# i2c0.net
KiCad netlist of a schematic drawn in Altium Designer
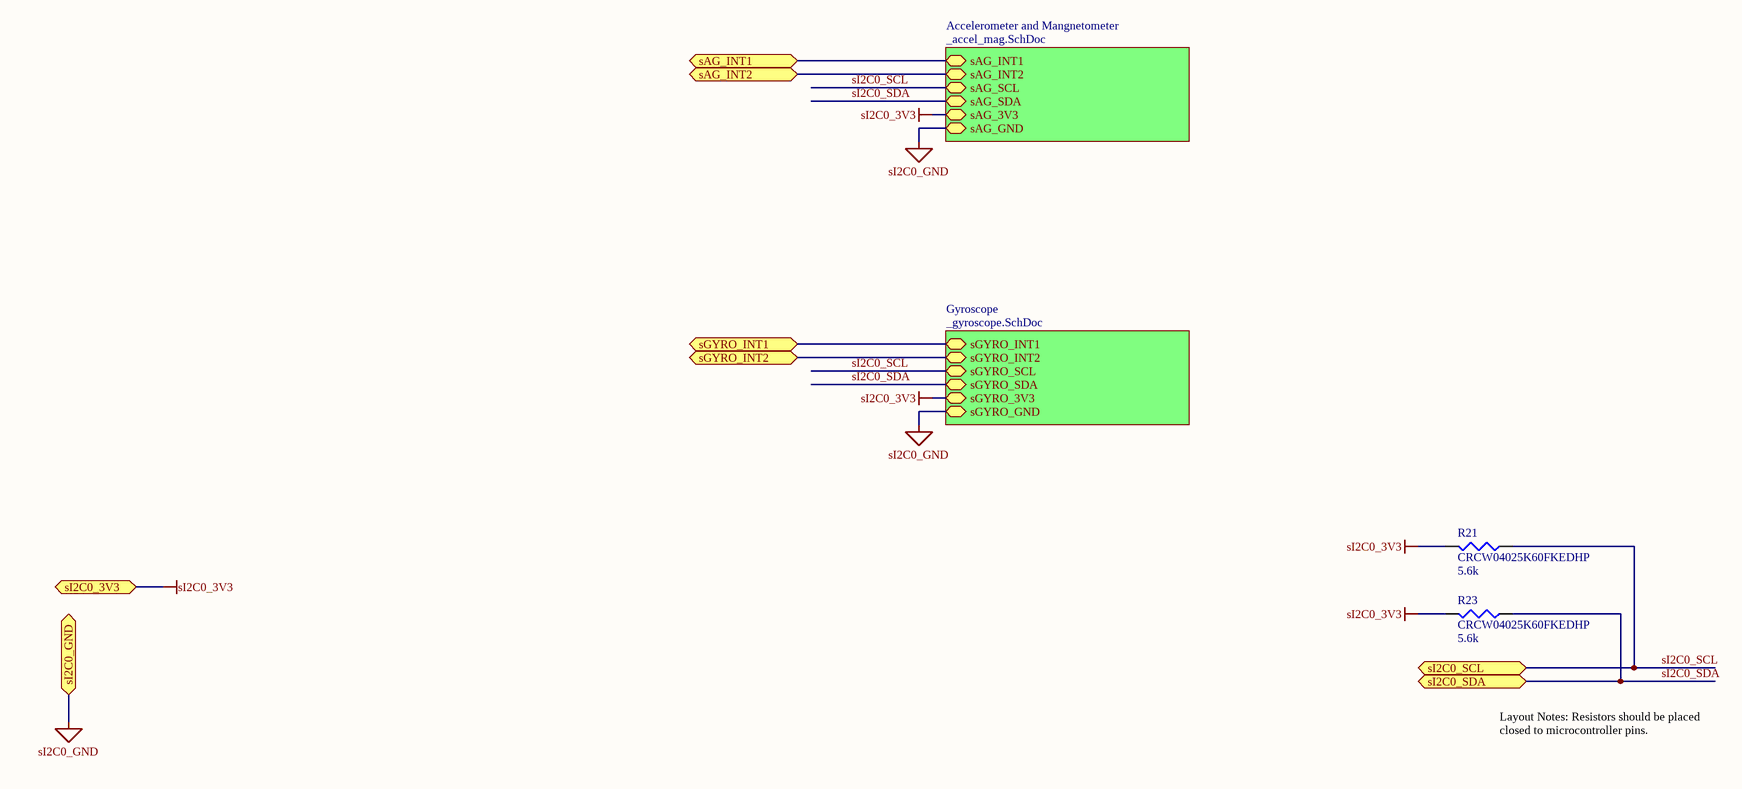
[diagram p0: _i2c0.SchDoc]

(export (version "E")
  (design (tool "Eeschema 10.0.6"))
  (components
    (comp (ref "R21")
      (value "CRCW04025K60FKEDHP")
      (footprint "0402")
      (description "0.125W, -55-155C, 1005, 50V, ±1%")
      (fields (field (name "ALTIUM_VALUE") "5.6k"))
      (libsource (lib "standard_resistors") (part "CRCW0402xxxxFKED"))
    )
    (comp (ref "R23")
      (value "CRCW04025K60FKEDHP")
      (footprint "0402")
      (description "0.125W, -55-155C, 1005, 50V, ±1%")
      (fields (field (name "ALTIUM_VALUE") "5.6k"))
      (libsource (lib "standard_resistors") (part "CRCW0402xxxxFKED"))
    )
  )
  (nets
    (net (code "5") (name "/sI2C0_SCL") (class "Default")
      (node (ref "R21") (pin "1") (pinfunction "1_1") (pintype "passive"))
    )
    (net (code "6") (name "/sI2C0_SDA") (class "Default")
      (node (ref "R23") (pin "1") (pinfunction "1_1") (pintype "passive"))
    )
    (net (code "7") (name "sI2C0_3V3") (class "Default")
      (node (ref "R21") (pin "2") (pinfunction "2_2") (pintype "passive"))
      (node (ref "R23") (pin "2") (pinfunction "2_2") (pintype "passive"))
    )
  )
)
